# demo1.net
KiCad netlist of a schematic drawn in EasyEDA Pro
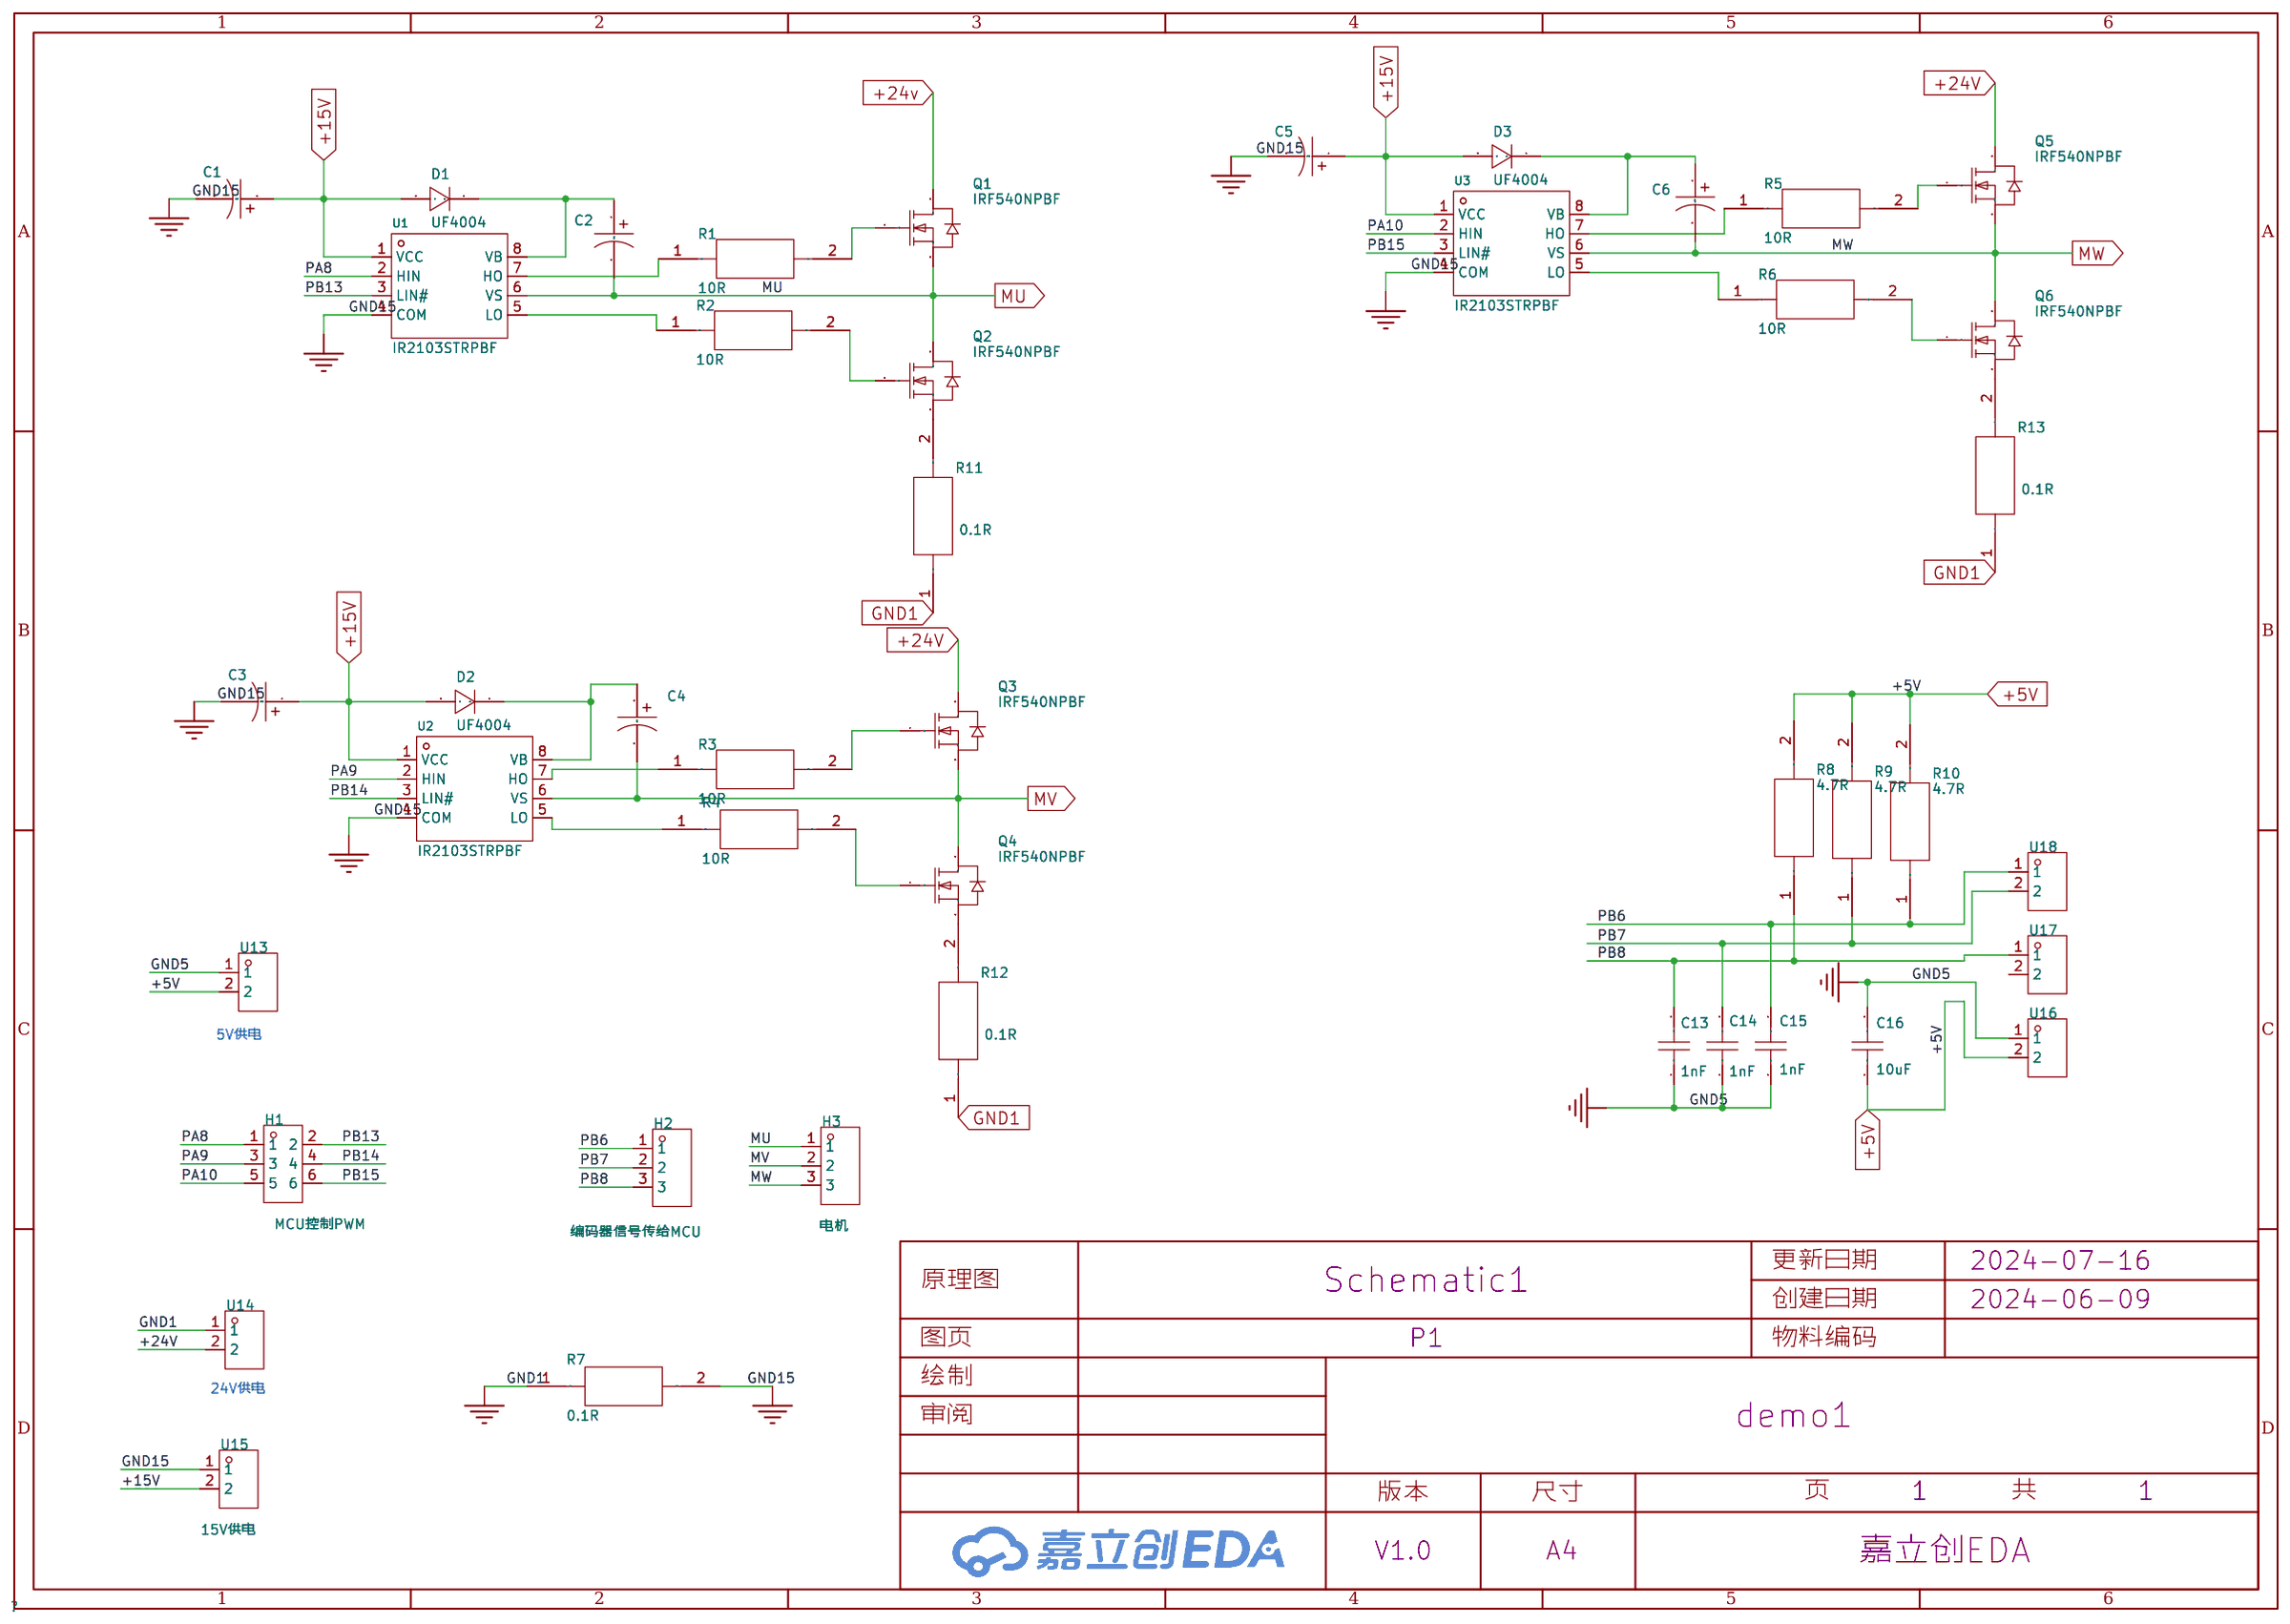
[diagram p0: schematic sheet]

(export (version "E")
  (design (tool "Eeschema 10.0.6"))
  (components
    (comp (ref "C1")
      (value "~")
      (footprint "easyedapro:钽电容")
      (libsource (lib "easyedapro") (part "10UF 25V"))
    )
    (comp (ref "C2")
      (value "~")
      (footprint "easyedapro:钽电容")
      (libsource (lib "easyedapro") (part "10UF 25V"))
    )
    (comp (ref "C3")
      (value "~")
      (footprint "easyedapro:钽电容")
      (libsource (lib "easyedapro") (part "10UF 25V"))
    )
    (comp (ref "C4")
      (value "~")
      (footprint "easyedapro:钽电容")
      (libsource (lib "easyedapro") (part "10UF 25V"))
    )
    (comp (ref "C5")
      (value "~")
      (footprint "easyedapro:钽电容")
      (libsource (lib "easyedapro") (part "10UF 25V"))
    )
    (comp (ref "C6")
      (value "~")
      (footprint "easyedapro:钽电容")
      (libsource (lib "easyedapro") (part "10UF 25V"))
    )
    (comp (ref "C13")
      (value "1nF")
      (footprint "easyedapro:独石电容")
      (libsource (lib "easyedapro") (part "10UF"))
    )
    (comp (ref "C14")
      (value "1nF")
      (footprint "easyedapro:独石电容")
      (libsource (lib "easyedapro") (part "10UF"))
    )
    (comp (ref "C15")
      (value "1nF")
      (footprint "easyedapro:独石电容")
      (libsource (lib "easyedapro") (part "10UF"))
    )
    (comp (ref "C16")
      (value "10uF")
      (footprint "easyedapro:独石电容")
      (libsource (lib "easyedapro") (part "10UF"))
    )
    (comp (ref "D1")
      (value "UF4004")
      (footprint "easyedapro:DO-41_BD2.4-L4.7-P8.70-D0.9-RD")
      (description "二极管配置:-;正向压降(Vf):1V@1A;直流反向耐压(Vr):400V;平均整流电流(Io):1A;")
      (fields (field (name "Manufacturer") "LGE(鲁光)"))
      (libsource (lib "easyedapro") (part "UF4004"))
    )
    (comp (ref "D2")
      (value "UF4004")
      (footprint "easyedapro:DO-41_BD2.4-L4.7-P8.70-D0.9-RD")
      (description "二极管配置:-;正向压降(Vf):1V@1A;直流反向耐压(Vr):400V;平均整流电流(Io):1A;")
      (fields (field (name "Manufacturer") "LGE(鲁光)"))
      (libsource (lib "easyedapro") (part "UF4004"))
    )
    (comp (ref "D3")
      (value "UF4004")
      (footprint "easyedapro:DO-41_BD2.4-L4.7-P8.70-D0.9-RD")
      (description "二极管配置:-;正向压降(Vf):1V@1A;直流反向耐压(Vr):400V;平均整流电流(Io):1A;")
      (fields (field (name "Manufacturer") "LGE(鲁光)"))
      (libsource (lib "easyedapro") (part "UF4004"))
    )
    (comp (ref "H1")
      (value "MCU控制PWM")
      (footprint "easyedapro:HDR-TH_6P-P2.54-V-M-R2-C3-S2.54")
      (fields (field (name "Manufacturer") "XFCN(兴飞)"))
      (libsource (lib "easyedapro") (part "PZ254V-12-6P"))
    )
    (comp (ref "H2")
      (value "编码器信号传给MCU")
      (footprint "easyedapro:HDR-TH_3P-P2.54-V-M")
      (fields (field (name "Manufacturer") "XFCN(兴飞)"))
      (libsource (lib "easyedapro") (part "PZ254V-11-03P_C2937625"))
    )
    (comp (ref "H3")
      (value "电机")
      (footprint "easyedapro:HDR-TH_3P-P2.54-V-M")
      (fields (field (name "Manufacturer") "XFCN(兴飞)"))
      (libsource (lib "easyedapro") (part "PZ254V-11-03P_C2937625"))
    )
    (comp (ref "Q1")
      (value "IRF540NPBF")
      (footprint "easyedapro:TO-220-3_L10.0-W4.5-P2.54-L")
      (fields (field (name "Manufacturer") "Infineon(英飞凌)"))
      (libsource (lib "easyedapro") (part "IRF540NPBF"))
    )
    (comp (ref "Q2")
      (value "IRF540NPBF")
      (footprint "easyedapro:TO-220-3_L10.0-W4.5-P2.54-L")
      (fields (field (name "Manufacturer") "Infineon(英飞凌)"))
      (libsource (lib "easyedapro") (part "IRF540NPBF"))
    )
    (comp (ref "Q3")
      (value "IRF540NPBF")
      (footprint "easyedapro:TO-220-3_L10.0-W4.5-P2.54-L")
      (fields (field (name "Manufacturer") "Infineon(英飞凌)"))
      (libsource (lib "easyedapro") (part "IRF540NPBF"))
    )
    (comp (ref "Q4")
      (value "IRF540NPBF")
      (footprint "easyedapro:TO-220-3_L10.0-W4.5-P2.54-L")
      (fields (field (name "Manufacturer") "Infineon(英飞凌)"))
      (libsource (lib "easyedapro") (part "IRF540NPBF"))
    )
    (comp (ref "Q5")
      (value "IRF540NPBF")
      (footprint "easyedapro:TO-220-3_L10.0-W4.5-P2.54-L")
      (fields (field (name "Manufacturer") "Infineon(英飞凌)"))
      (libsource (lib "easyedapro") (part "IRF540NPBF"))
    )
    (comp (ref "Q6")
      (value "IRF540NPBF")
      (footprint "easyedapro:TO-220-3_L10.0-W4.5-P2.54-L")
      (fields (field (name "Manufacturer") "Infineon(英飞凌)"))
      (libsource (lib "easyedapro") (part "IRF540NPBF"))
    )
    (comp (ref "R1") (value "10R") (description "电阻") (libsource (lib "easyedapro") (part "电阻")))
    (comp (ref "R2") (value "10R") (description "电阻") (libsource (lib "easyedapro") (part "电阻")))
    (comp (ref "R3") (value "10R") (description "电阻") (libsource (lib "easyedapro") (part "电阻")))
    (comp (ref "R4") (value "10R") (description "电阻") (libsource (lib "easyedapro") (part "电阻")))
    (comp (ref "R5") (value "10R") (description "电阻") (libsource (lib "easyedapro") (part "电阻")))
    (comp (ref "R6") (value "10R") (description "电阻") (libsource (lib "easyedapro") (part "电阻")))
    (comp (ref "R7") (value "0.1R") (description "电阻") (libsource (lib "easyedapro") (part "电阻")))
    (comp (ref "R8") (value "4.7R") (description "电阻") (libsource (lib "easyedapro") (part "电阻")))
    (comp (ref "R9") (value "4.7R") (description "电阻") (libsource (lib "easyedapro") (part "电阻")))
    (comp (ref "R10") (value "4.7R") (description "电阻") (libsource (lib "easyedapro") (part "电阻")))
    (comp (ref "R11") (value "0.1R") (description "电阻") (libsource (lib "easyedapro") (part "电阻")))
    (comp (ref "R12") (value "0.1R") (description "电阻") (libsource (lib "easyedapro") (part "电阻")))
    (comp (ref "R13") (value "0.1R") (description "电阻") (libsource (lib "easyedapro") (part "电阻")))
    (comp (ref "U1")
      (value "IR2103STRPBF")
      (footprint "easyedapro:SOIC-8_L4.9-W3.9-P1.27-LS6.0-BL")
      (description "驱动配置:半桥;负载类型:MOSFET；IGBT;驱动通道数:2;峰值灌电流:360mA;峰值拉电流:210mA;电源电压:10V~20V;上升时间:100ns;下降时间:50ns;")
      (fields (field (name "Manufacturer") "Infineon(英飞凌)"))
      (libsource (lib "easyedapro") (part "IR2103STRPBF"))
    )
    (comp (ref "U2")
      (value "IR2103STRPBF")
      (footprint "easyedapro:SOIC-8_L4.9-W3.9-P1.27-LS6.0-BL")
      (description "驱动配置:半桥;负载类型:MOSFET；IGBT;驱动通道数:2;峰值灌电流:360mA;峰值拉电流:210mA;电源电压:10V~20V;上升时间:100ns;下降时间:50ns;")
      (fields (field (name "Manufacturer") "Infineon(英飞凌)"))
      (libsource (lib "easyedapro") (part "IR2103STRPBF"))
    )
    (comp (ref "U3")
      (value "IR2103STRPBF")
      (footprint "easyedapro:SOIC-8_L4.9-W3.9-P1.27-LS6.0-BL")
      (description "驱动配置:半桥;负载类型:MOSFET；IGBT;驱动通道数:2;峰值灌电流:360mA;峰值拉电流:210mA;电源电压:10V~20V;上升时间:100ns;下降时间:50ns;")
      (fields (field (name "Manufacturer") "Infineon(英飞凌)"))
      (libsource (lib "easyedapro") (part "IR2103STRPBF"))
    )
    (comp (ref "U13")
      (value "DB125-3.81-2P-GN-S")
      (footprint "easyedapro:CONN-TH_2P-P3.81_L7.4-W7.6")
      (fields (field (name "Manufacturer") "DORABO(地博电气)"))
      (libsource (lib "easyedapro") (part "DB125-3.81-2P"))
    )
    (comp (ref "U14")
      (value "DB125-3.81-2P-GN-S")
      (footprint "easyedapro:CONN-TH_2P-P3.81_L7.4-W7.6")
      (fields (field (name "Manufacturer") "DORABO(地博电气)"))
      (libsource (lib "easyedapro") (part "DB125-3.81-2P"))
    )
    (comp (ref "U15")
      (value "15V供电")
      (footprint "easyedapro:CONN-TH_2P-P3.81_L7.4-W7.6")
      (fields (field (name "Manufacturer") "DORABO(地博电气)"))
      (libsource (lib "easyedapro") (part "DB125-3.81-2P"))
    )
    (comp (ref "U16")
      (value "DB125-3.81-2P-GN-S")
      (footprint "easyedapro:CONN-TH_2P-P3.81_L7.4-W7.6")
      (fields (field (name "Manufacturer") "DORABO(地博电气)"))
      (libsource (lib "easyedapro") (part "DB125-3.81-2P"))
    )
    (comp (ref "U17")
      (value "DB125-3.81-2P-GN-S")
      (footprint "easyedapro:CONN-TH_2P-P3.81_L7.4-W7.6")
      (fields (field (name "Manufacturer") "DORABO(地博电气)"))
      (libsource (lib "easyedapro") (part "DB125-3.81-2P"))
    )
    (comp (ref "U18")
      (value "DB125-3.81-2P-GN-S")
      (footprint "easyedapro:CONN-TH_2P-P3.81_L7.4-W7.6")
      (fields (field (name "Manufacturer") "DORABO(地博电气)"))
      (libsource (lib "easyedapro") (part "DB125-3.81-2P"))
    )
  )
  (nets
    (net (code "1") (name "+5V") (class "Default")
      (node (ref "C16") (pin "1") (pinfunction "1_1") (pintype "unspecified"))
      (node (ref "R10") (pin "2") (pinfunction "2_2") (pintype "input"))
      (node (ref "R8") (pin "2") (pinfunction "2_2") (pintype "input"))
      (node (ref "R9") (pin "2") (pinfunction "2_2") (pintype "input"))
      (node (ref "U13") (pin "2") (pinfunction "2_2") (pintype "unspecified"))
      (node (ref "U16") (pin "2") (pinfunction "2_2") (pintype "unspecified"))
    )
    (net (code "2") (name "+15V") (class "Default")
      (node (ref "C1") (pin "1") (pinfunction "1_1") (pintype "unspecified"))
      (node (ref "C3") (pin "1") (pinfunction "1_1") (pintype "unspecified"))
      (node (ref "C5") (pin "1") (pinfunction "1_1") (pintype "unspecified"))
      (node (ref "D1") (pin "2") (pinfunction "A_2") (pintype "unspecified"))
      (node (ref "D2") (pin "2") (pinfunction "A_2") (pintype "unspecified"))
      (node (ref "D3") (pin "2") (pinfunction "A_2") (pintype "unspecified"))
      (node (ref "U1") (pin "1") (pinfunction "VCC_1") (pintype "input"))
      (node (ref "U15") (pin "2") (pinfunction "2_2") (pintype "unspecified"))
      (node (ref "U2") (pin "1") (pinfunction "VCC_1") (pintype "input"))
      (node (ref "U3") (pin "1") (pinfunction "VCC_1") (pintype "input"))
    )
    (net (code "3") (name "+24V") (class "Default")
      (node (ref "Q3") (pin "2") (pinfunction "D_2") (pintype "input"))
      (node (ref "Q5") (pin "2") (pinfunction "D_2") (pintype "input"))
      (node (ref "U14") (pin "2") (pinfunction "2_2") (pintype "unspecified"))
    )
    (net (code "4") (name "+24v") (class "Default")
      (node (ref "Q1") (pin "2") (pinfunction "D_2") (pintype "input"))
    )
    (net (code "5") (name "/PA8") (class "Default")
      (node (ref "H1") (pin "1") (pinfunction "1_1") (pintype "unspecified"))
      (node (ref "U1") (pin "2") (pinfunction "HIN_2") (pintype "input"))
    )
    (net (code "6") (name "/PA9") (class "Default")
      (node (ref "H1") (pin "3") (pinfunction "3_3") (pintype "unspecified"))
      (node (ref "U2") (pin "2") (pinfunction "HIN_2") (pintype "input"))
    )
    (net (code "7") (name "/PA10") (class "Default")
      (node (ref "H1") (pin "5") (pinfunction "5_5") (pintype "unspecified"))
      (node (ref "U3") (pin "2") (pinfunction "HIN_2") (pintype "input"))
    )
    (net (code "8") (name "/PB6") (class "Default")
      (node (ref "C15") (pin "2") (pinfunction "2_2") (pintype "unspecified"))
      (node (ref "H2") (pin "1") (pinfunction "1_1") (pintype "unspecified"))
      (node (ref "R10") (pin "1") (pinfunction "1_1") (pintype "input"))
      (node (ref "U18") (pin "1") (pinfunction "1_1") (pintype "unspecified"))
    )
    (net (code "9") (name "/PB7") (class "Default")
      (node (ref "C14") (pin "2") (pinfunction "2_2") (pintype "unspecified"))
      (node (ref "H2") (pin "2") (pinfunction "2_2") (pintype "unspecified"))
      (node (ref "R9") (pin "1") (pinfunction "1_1") (pintype "input"))
      (node (ref "U18") (pin "2") (pinfunction "2_2") (pintype "unspecified"))
    )
    (net (code "10") (name "/PB8") (class "Default")
      (node (ref "C13") (pin "2") (pinfunction "2_2") (pintype "unspecified"))
      (node (ref "H2") (pin "3") (pinfunction "3_3") (pintype "unspecified"))
      (node (ref "R8") (pin "1") (pinfunction "1_1") (pintype "input"))
      (node (ref "U17") (pin "1") (pinfunction "1_1") (pintype "unspecified"))
    )
    (net (code "11") (name "/PB13") (class "Default")
      (node (ref "H1") (pin "2") (pinfunction "2_2") (pintype "unspecified"))
      (node (ref "U1") (pin "3") (pinfunction "LIN#_3") (pintype "input"))
    )
    (net (code "12") (name "/PB14") (class "Default")
      (node (ref "H1") (pin "4") (pinfunction "4_4") (pintype "unspecified"))
      (node (ref "U2") (pin "3") (pinfunction "LIN#_3") (pintype "input"))
    )
    (net (code "13") (name "/PB15") (class "Default")
      (node (ref "H1") (pin "6") (pinfunction "6_6") (pintype "unspecified"))
      (node (ref "U3") (pin "3") (pinfunction "LIN#_3") (pintype "input"))
    )
    (net (code "14") (name "GND1") (class "Default")
      (node (ref "R11") (pin "1") (pinfunction "1_1") (pintype "input"))
      (node (ref "R12") (pin "1") (pinfunction "1_1") (pintype "input"))
      (node (ref "R13") (pin "1") (pinfunction "1_1") (pintype "input"))
      (node (ref "R7") (pin "1") (pinfunction "1_1") (pintype "input"))
      (node (ref "U14") (pin "1") (pinfunction "1_1") (pintype "unspecified"))
    )
    (net (code "15") (name "GND5") (class "Default")
      (node (ref "C13") (pin "1") (pinfunction "1_1") (pintype "unspecified"))
      (node (ref "C14") (pin "1") (pinfunction "1_1") (pintype "unspecified"))
      (node (ref "C15") (pin "1") (pinfunction "1_1") (pintype "unspecified"))
      (node (ref "C16") (pin "2") (pinfunction "2_2") (pintype "unspecified"))
      (node (ref "U13") (pin "1") (pinfunction "1_1") (pintype "unspecified"))
      (node (ref "U16") (pin "1") (pinfunction "1_1") (pintype "unspecified"))
    )
    (net (code "16") (name "GND15") (class "Default")
      (node (ref "C1") (pin "2") (pinfunction "2_2") (pintype "unspecified"))
      (node (ref "C3") (pin "2") (pinfunction "2_2") (pintype "unspecified"))
      (node (ref "C5") (pin "2") (pinfunction "2_2") (pintype "unspecified"))
      (node (ref "R7") (pin "2") (pinfunction "2_2") (pintype "input"))
      (node (ref "U1") (pin "4") (pinfunction "COM_4") (pintype "input"))
      (node (ref "U15") (pin "1") (pinfunction "1_1") (pintype "unspecified"))
      (node (ref "U2") (pin "4") (pinfunction "COM_4") (pintype "input"))
      (node (ref "U3") (pin "4") (pinfunction "COM_4") (pintype "input"))
    )
    (net (code "17") (name "MU") (class "Default")
      (node (ref "C2") (pin "2") (pinfunction "2_2") (pintype "unspecified"))
      (node (ref "H3") (pin "1") (pinfunction "1_1") (pintype "unspecified"))
      (node (ref "Q1") (pin "3") (pinfunction "S_3") (pintype "input"))
      (node (ref "Q2") (pin "2") (pinfunction "D_2") (pintype "input"))
      (node (ref "U1") (pin "6") (pinfunction "VS_6") (pintype "input"))
    )
    (net (code "18") (name "MV") (class "Default")
      (node (ref "C4") (pin "2") (pinfunction "2_2") (pintype "unspecified"))
      (node (ref "H3") (pin "2") (pinfunction "2_2") (pintype "unspecified"))
      (node (ref "Q3") (pin "3") (pinfunction "S_3") (pintype "input"))
      (node (ref "Q4") (pin "2") (pinfunction "D_2") (pintype "input"))
      (node (ref "U2") (pin "6") (pinfunction "VS_6") (pintype "input"))
    )
    (net (code "19") (name "MW") (class "Default")
      (node (ref "C6") (pin "2") (pinfunction "2_2") (pintype "unspecified"))
      (node (ref "H3") (pin "3") (pinfunction "3_3") (pintype "unspecified"))
      (node (ref "Q5") (pin "3") (pinfunction "S_3") (pintype "input"))
      (node (ref "Q6") (pin "2") (pinfunction "D_2") (pintype "input"))
      (node (ref "U3") (pin "6") (pinfunction "VS_6") (pintype "input"))
    )
    (net (code "20") (name "Net-(D1-C)") (class "Default")
      (node (ref "C2") (pin "1") (pinfunction "1_1") (pintype "unspecified"))
      (node (ref "D1") (pin "1") (pinfunction "C_1") (pintype "unspecified"))
      (node (ref "U1") (pin "8") (pinfunction "VB_8") (pintype "input"))
    )
    (net (code "21") (name "Net-(D2-C)") (class "Default")
      (node (ref "C4") (pin "1") (pinfunction "1_1") (pintype "unspecified"))
      (node (ref "D2") (pin "1") (pinfunction "C_1") (pintype "unspecified"))
      (node (ref "U2") (pin "8") (pinfunction "VB_8") (pintype "input"))
    )
    (net (code "22") (name "Net-(D3-C)") (class "Default")
      (node (ref "C6") (pin "1") (pinfunction "1_1") (pintype "unspecified"))
      (node (ref "D3") (pin "1") (pinfunction "C_1") (pintype "unspecified"))
      (node (ref "U3") (pin "8") (pinfunction "VB_8") (pintype "input"))
    )
    (net (code "23") (name "Net-(Q1-G)") (class "Default")
      (node (ref "Q1") (pin "1") (pinfunction "G_1") (pintype "input"))
      (node (ref "R1") (pin "2") (pinfunction "2_2") (pintype "input"))
    )
    (net (code "24") (name "Net-(Q2-G)") (class "Default")
      (node (ref "Q2") (pin "1") (pinfunction "G_1") (pintype "input"))
      (node (ref "R2") (pin "2") (pinfunction "2_2") (pintype "input"))
    )
    (net (code "25") (name "Net-(Q2-S)") (class "Default")
      (node (ref "Q2") (pin "3") (pinfunction "S_3") (pintype "input"))
      (node (ref "R11") (pin "2") (pinfunction "2_2") (pintype "input"))
    )
    (net (code "26") (name "Net-(Q3-G)") (class "Default")
      (node (ref "Q3") (pin "1") (pinfunction "G_1") (pintype "input"))
      (node (ref "R3") (pin "2") (pinfunction "2_2") (pintype "input"))
    )
    (net (code "27") (name "Net-(Q4-G)") (class "Default")
      (node (ref "Q4") (pin "1") (pinfunction "G_1") (pintype "input"))
      (node (ref "R4") (pin "2") (pinfunction "2_2") (pintype "input"))
    )
    (net (code "28") (name "Net-(Q4-S)") (class "Default")
      (node (ref "Q4") (pin "3") (pinfunction "S_3") (pintype "input"))
      (node (ref "R12") (pin "2") (pinfunction "2_2") (pintype "input"))
    )
    (net (code "29") (name "Net-(Q5-G)") (class "Default")
      (node (ref "Q5") (pin "1") (pinfunction "G_1") (pintype "input"))
      (node (ref "R5") (pin "2") (pinfunction "2_2") (pintype "input"))
    )
    (net (code "30") (name "Net-(Q6-G)") (class "Default")
      (node (ref "Q6") (pin "1") (pinfunction "G_1") (pintype "input"))
      (node (ref "R6") (pin "2") (pinfunction "2_2") (pintype "input"))
    )
    (net (code "31") (name "Net-(Q6-S)") (class "Default")
      (node (ref "Q6") (pin "3") (pinfunction "S_3") (pintype "input"))
      (node (ref "R13") (pin "2") (pinfunction "2_2") (pintype "input"))
    )
    (net (code "32") (name "Net-(U1-HO)") (class "Default")
      (node (ref "R1") (pin "1") (pinfunction "1_1") (pintype "input"))
      (node (ref "U1") (pin "7") (pinfunction "HO_7") (pintype "input"))
    )
    (net (code "33") (name "Net-(U1-LO)") (class "Default")
      (node (ref "R2") (pin "1") (pinfunction "1_1") (pintype "input"))
      (node (ref "U1") (pin "5") (pinfunction "LO_5") (pintype "input"))
    )
    (net (code "34") (name "Net-(U2-HO)") (class "Default")
      (node (ref "R3") (pin "1") (pinfunction "1_1") (pintype "input"))
      (node (ref "U2") (pin "7") (pinfunction "HO_7") (pintype "input"))
    )
    (net (code "35") (name "Net-(U2-LO)") (class "Default")
      (node (ref "R4") (pin "1") (pinfunction "1_1") (pintype "input"))
      (node (ref "U2") (pin "5") (pinfunction "LO_5") (pintype "input"))
    )
    (net (code "36") (name "Net-(U3-HO)") (class "Default")
      (node (ref "R5") (pin "1") (pinfunction "1_1") (pintype "input"))
      (node (ref "U3") (pin "7") (pinfunction "HO_7") (pintype "input"))
    )
    (net (code "37") (name "Net-(U3-LO)") (class "Default")
      (node (ref "R6") (pin "1") (pinfunction "1_1") (pintype "input"))
      (node (ref "U3") (pin "5") (pinfunction "LO_5") (pintype "input"))
    )
    (net (code "38") (name "unconnected-(U17-Pad2)") (class "Default")
      (node (ref "U17") (pin "2") (pinfunction "2_2") (pintype "unspecified"))
    )
  )
)
